# TMC2208_TEST.net
KiCad netlist of a schematic drawn in Altium Designer
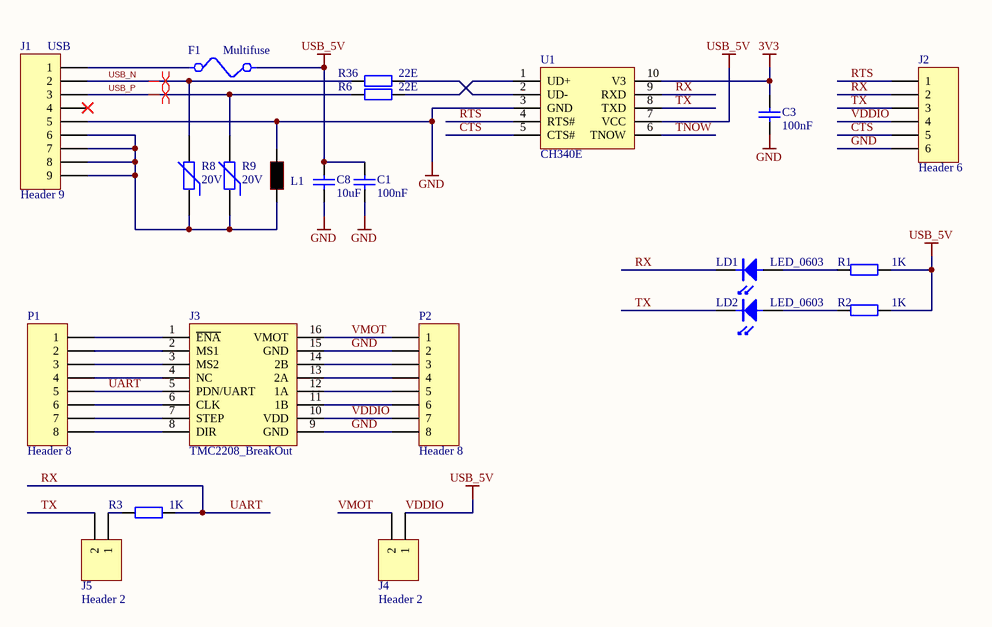
[diagram p0: TMC2208_TEST.SchDoc]

(export (version "E")
  (design (tool "Eeschema 10.0.6"))
  (components
    (comp (ref "C1")
      (value "100nF")
      (footprint "CAP0603")
      (description "RO X7R 100nF 10% 50V 0603")
      (libsource (lib "Ultimaker") (part "Capacitor"))
    )
    (comp (ref "C3")
      (value "100nF")
      (footprint "CAP0603")
      (description "RO X5R 1uF 10% 10V 0603")
      (libsource (lib "Ultimaker") (part "Capacitor"))
    )
    (comp (ref "C8")
      (value "10uF")
      (footprint "CAP0603")
      (description "RO X7R 100nF 10% 50V 0603")
      (libsource (lib "Ultimaker") (part "Capacitor"))
    )
    (comp (ref "F1")
      (value "Multifuse")
      (footprint "Multifuse1812")
      (description "RO ZEK MULTI 500MA SMD 1812 MF-MSMF050-2 BOURNS")
      (fields (field (name "MFG") "BOURNS"))
      (libsource (lib "Ultimaker") (part "Multifuse"))
    )
    (comp (ref "J1")
      (value "Header 9")
      (footprint "MicroUSB")
      (description "Header, 9-Pin")
      (fields (field (name "PUBLISHER") "Altium Limited"))
      (libsource (lib "Miscellaneous Connectors") (part "Header 9"))
    )
    (comp (ref "J2")
      (value "Header 6")
      (footprint "HDR1X6")
      (description "Header, 6-Pin")
      (fields (field (name "PUBLISHER") "Altium Limited"))
      (libsource (lib "Miscellaneous Connectors") (part "Header 6"))
    )
    (comp (ref "J3")
      (value "TMC2208_BreakOut")
      (footprint "TMC2208")
      (libsource (lib "接插件库") (part "TMC2208_BreakOut"))
    )
    (comp (ref "J4")
      (value "Header 2")
      (footprint "HDR1X2")
      (description "Header, 2-Pin")
      (fields (field (name "PUBLISHER") "Altium Limited"))
      (libsource (lib "Miscellaneous Connectors") (part "Header 2"))
    )
    (comp (ref "J5")
      (value "Header 2")
      (footprint "HDR1X2")
      (description "Header, 2-Pin")
      (fields (field (name "PUBLISHER") "Altium Limited"))
      (libsource (lib "Miscellaneous Connectors") (part "Header 2"))
    )
    (comp (ref "L1")
      (value "Bead")
      (footprint "L0805")
      (description "RO FERRIET BLM21PG221SN1D  0805")
      (libsource (lib "Ultimaker") (part "Bead"))
    )
    (comp (ref "LD1") (value "LED_0603") (footprint "LED0603") (libsource (lib "接插件库") (part "LED_0603")))
    (comp (ref "LD2") (value "LED_0603") (footprint "LED0603") (libsource (lib "接插件库") (part "LED_0603")))
    (comp (ref "P1")
      (value "Header 8")
      (footprint "Header 1X8")
      (description "Header, 8-Pin")
      (fields (field (name "PUBLISHER") "Altium Limited"))
      (libsource (lib "") (part "Header 8_1"))
    )
    (comp (ref "P2")
      (value "Header 8")
      (footprint "Header 1X8")
      (description "Header, 8-Pin")
      (fields (field (name "PUBLISHER") "Altium Limited"))
      (libsource (lib "Miscellaneous Connectors") (part "Header 8"))
    )
    (comp (ref "R1")
      (value "1K")
      (footprint "RES0603")
      (description "RO RES 22E0 1% 0,063W 0603")
      (libsource (lib "") (part "Resistor_1"))
    )
    (comp (ref "R2")
      (value "1K")
      (footprint "RES0603")
      (description "RO RES 22E0 1% 0,063W 0603")
      (libsource (lib "") (part "Resistor_1"))
    )
    (comp (ref "R3")
      (value "1K")
      (footprint "RES0603")
      (description "RO RES 22E0 1% 0,063W 0603")
      (libsource (lib "Ultimaker") (part "Resistor"))
    )
    (comp (ref "R6")
      (value "22E")
      (footprint "RES0603")
      (description "RO RES 22E0 1% 0,063W 0603")
      (libsource (lib "Ultimaker") (part "Resistor"))
    )
    (comp (ref "R8")
      (value "20V")
      (footprint "RES0603")
      (description "RO VDR 0603 CG0603MLC-05E")
      (fields (field (name "MFG") "BOURNS"))
      (libsource (lib "Ultimaker") (part "Varistor"))
    )
    (comp (ref "R9")
      (value "20V")
      (footprint "RES0603")
      (description "RO VDR 0603 CG0603MLC-05E")
      (fields (field (name "MFG") "BOURNS"))
      (libsource (lib "Ultimaker") (part "Varistor"))
    )
    (comp (ref "R36")
      (value "22E")
      (footprint "RES0603")
      (description "RO RES 22E0 1% 0,063W 0603")
      (libsource (lib "Ultimaker") (part "Resistor"))
    )
    (comp (ref "U1") (value "CH340E") (footprint "MSOP10") (libsource (lib "接插件库") (part "CH340E")))
  )
  (nets
    (net (code "1") (name "/CTS") (class "Default")
      (node (ref "J2") (pin "5") (pinfunction "5_5") (pintype "passive"))
      (node (ref "U1") (pin "5") (pinfunction "CTS#_5") (pintype "passive"))
    )
    (net (code "2") (name "/RTS") (class "Default")
      (node (ref "J2") (pin "1") (pinfunction "1_1") (pintype "passive"))
      (node (ref "U1") (pin "4") (pinfunction "RTS#_4") (pintype "passive"))
    )
    (net (code "3") (name "/RX") (class "Default")
      (node (ref "J2") (pin "2") (pinfunction "2_2") (pintype "passive"))
      (node (ref "J3") (pin "5") (pinfunction "PDN/UART_5") (pintype "passive"))
      (node (ref "LD1") (pin "1") (pinfunction "A_1") (pintype "passive"))
      (node (ref "P1") (pin "5") (pinfunction "5_5") (pintype "passive"))
      (node (ref "R3") (pin "2") (pinfunction "2_2") (pintype "passive"))
      (node (ref "U1") (pin "9") (pinfunction "RXD_9") (pintype "passive"))
    )
    (net (code "4") (name "/TNOW") (class "Default")
      (node (ref "U1") (pin "6") (pinfunction "TNOW_6") (pintype "passive"))
    )
    (net (code "5") (name "/TX") (class "Default")
      (node (ref "J2") (pin "3") (pinfunction "3_3") (pintype "passive"))
      (node (ref "J5") (pin "2") (pinfunction "2_2") (pintype "passive"))
      (node (ref "LD2") (pin "1") (pinfunction "A_1") (pintype "passive"))
      (node (ref "U1") (pin "8") (pinfunction "TXD_8") (pintype "passive"))
    )
    (net (code "6") (name "/USB_N") (class "Default")
      (node (ref "J1") (pin "2") (pinfunction "2_2") (pintype "passive"))
      (node (ref "R36") (pin "1") (pinfunction "1_1") (pintype "passive"))
      (node (ref "R8") (pin "2") (pinfunction "2_2") (pintype "passive"))
    )
    (net (code "7") (name "/USB_P") (class "Default")
      (node (ref "J1") (pin "3") (pinfunction "3_3") (pintype "passive"))
      (node (ref "R6") (pin "1") (pinfunction "1_1") (pintype "passive"))
      (node (ref "R9") (pin "2") (pinfunction "2_2") (pintype "passive"))
    )
    (net (code "8") (name "/VMOT") (class "Default")
      (node (ref "J3") (pin "16") (pinfunction "VMOT_16") (pintype "passive"))
      (node (ref "J4") (pin "2") (pinfunction "2_2") (pintype "passive"))
      (node (ref "P2") (pin "1") (pinfunction "1_1") (pintype "passive"))
    )
    (net (code "9") (name "3V3") (class "Default")
      (node (ref "C3") (pin "2") (pinfunction "2_2") (pintype "passive"))
      (node (ref "U1") (pin "10") (pinfunction "V3_10") (pintype "passive"))
    )
    (net (code "10") (name "GND") (class "Default")
      (node (ref "C1") (pin "2") (pinfunction "2_2") (pintype "passive"))
      (node (ref "C3") (pin "1") (pinfunction "1_1") (pintype "passive"))
      (node (ref "C8") (pin "1") (pinfunction "1_1") (pintype "passive"))
      (node (ref "J1") (pin "5") (pinfunction "5_5") (pintype "passive"))
      (node (ref "J2") (pin "6") (pinfunction "6_6") (pintype "passive"))
      (node (ref "J3") (pin "15") (pinfunction "GND_15") (pintype "passive"))
      (node (ref "J3") (pin "9") (pinfunction "GND_9") (pintype "passive"))
      (node (ref "L1") (pin "1") (pinfunction "1_1") (pintype "passive"))
      (node (ref "P2") (pin "2") (pinfunction "2_2") (pintype "passive"))
      (node (ref "P2") (pin "8") (pinfunction "8_8") (pintype "passive"))
      (node (ref "U1") (pin "3") (pinfunction "GND_3") (pintype "passive"))
    )
    (net (code "11") (name "Net-(F1-Pad1)") (class "Default")
      (node (ref "F1") (pin "1") (pinfunction "1_1") (pintype "passive"))
      (node (ref "J1") (pin "1") (pinfunction "1_1") (pintype "passive"))
    )
    (net (code "12") (name "Net-(J1-Pad6)") (class "Default")
      (node (ref "J1") (pin "6") (pinfunction "6_6") (pintype "passive"))
      (node (ref "J1") (pin "7") (pinfunction "7_7") (pintype "passive"))
      (node (ref "J1") (pin "8") (pinfunction "8_8") (pintype "passive"))
      (node (ref "J1") (pin "9") (pinfunction "9_9") (pintype "passive"))
      (node (ref "L1") (pin "2") (pinfunction "2_2") (pintype "passive"))
      (node (ref "R8") (pin "1") (pinfunction "1_1") (pintype "passive"))
      (node (ref "R9") (pin "1") (pinfunction "1_1") (pintype "passive"))
    )
    (net (code "13") (name "Net-(J3-1A)") (class "Default")
      (node (ref "J3") (pin "12") (pinfunction "1A_12") (pintype "passive"))
      (node (ref "P2") (pin "5") (pinfunction "5_5") (pintype "passive"))
    )
    (net (code "14") (name "Net-(J3-1B)") (class "Default")
      (node (ref "J3") (pin "11") (pinfunction "1B_11") (pintype "passive"))
      (node (ref "P2") (pin "6") (pinfunction "6_6") (pintype "passive"))
    )
    (net (code "15") (name "Net-(J3-2A)") (class "Default")
      (node (ref "J3") (pin "13") (pinfunction "2A_13") (pintype "passive"))
      (node (ref "P2") (pin "4") (pinfunction "4_4") (pintype "passive"))
    )
    (net (code "16") (name "Net-(J3-2B)") (class "Default")
      (node (ref "J3") (pin "14") (pinfunction "2B_14") (pintype "passive"))
      (node (ref "P2") (pin "3") (pinfunction "3_3") (pintype "passive"))
    )
    (net (code "17") (name "Net-(J3-CLK)") (class "Default")
      (node (ref "J3") (pin "6") (pinfunction "CLK_6") (pintype "passive"))
      (node (ref "P1") (pin "6") (pinfunction "6_6") (pintype "passive"))
    )
    (net (code "18") (name "Net-(J3-DIR)") (class "Default")
      (node (ref "J3") (pin "8") (pinfunction "DIR_8") (pintype "passive"))
      (node (ref "P1") (pin "8") (pinfunction "8_8") (pintype "passive"))
    )
    (net (code "19") (name "Net-(J3-MS1)") (class "Default")
      (node (ref "J3") (pin "2") (pinfunction "MS1_2") (pintype "passive"))
      (node (ref "P1") (pin "2") (pinfunction "2_2") (pintype "passive"))
    )
    (net (code "20") (name "Net-(J3-MS2)") (class "Default")
      (node (ref "J3") (pin "3") (pinfunction "MS2_3") (pintype "passive"))
      (node (ref "P1") (pin "3") (pinfunction "3_3") (pintype "passive"))
    )
    (net (code "21") (name "Net-(J3-NC)") (class "Default")
      (node (ref "J3") (pin "4") (pinfunction "NC_4") (pintype "passive"))
      (node (ref "P1") (pin "4") (pinfunction "4_4") (pintype "passive"))
    )
    (net (code "22") (name "Net-(J3-STEP)") (class "Default")
      (node (ref "J3") (pin "7") (pinfunction "STEP_7") (pintype "passive"))
      (node (ref "P1") (pin "7") (pinfunction "7_7") (pintype "passive"))
    )
    (net (code "23") (name "Net-(J3-~{ENA})") (class "Default")
      (node (ref "J3") (pin "1") (pinfunction "~{ENA}_1") (pintype "passive"))
      (node (ref "P1") (pin "1") (pinfunction "1_1") (pintype "passive"))
    )
    (net (code "24") (name "Net-(J5-Pad1)") (class "Default")
      (node (ref "J5") (pin "1") (pinfunction "1_1") (pintype "passive"))
      (node (ref "R3") (pin "1") (pinfunction "1_1") (pintype "passive"))
    )
    (net (code "25") (name "Net-(LD1-K)") (class "Default")
      (node (ref "LD1") (pin "2") (pinfunction "K_2") (pintype "passive"))
      (node (ref "R1") (pin "2") (pinfunction "2_2") (pintype "passive"))
    )
    (net (code "26") (name "Net-(LD2-K)") (class "Default")
      (node (ref "LD2") (pin "2") (pinfunction "K_2") (pintype "passive"))
      (node (ref "R2") (pin "2") (pinfunction "2_2") (pintype "passive"))
    )
    (net (code "27") (name "Net-(U1-UD+)") (class "Default")
      (node (ref "R6") (pin "2") (pinfunction "2_2") (pintype "passive"))
      (node (ref "U1") (pin "1") (pinfunction "UD+_1") (pintype "passive"))
    )
    (net (code "28") (name "Net-(U1-UD-)") (class "Default")
      (node (ref "R36") (pin "2") (pinfunction "2_2") (pintype "passive"))
      (node (ref "U1") (pin "2") (pinfunction "UD-_2") (pintype "passive"))
    )
    (net (code "29") (name "USB_5V") (class "Default")
      (node (ref "C1") (pin "1") (pinfunction "1_1") (pintype "passive"))
      (node (ref "C8") (pin "2") (pinfunction "2_2") (pintype "passive"))
      (node (ref "F1") (pin "2") (pinfunction "2_2") (pintype "passive"))
      (node (ref "J2") (pin "4") (pinfunction "4_4") (pintype "passive"))
      (node (ref "J3") (pin "10") (pinfunction "VDD_10") (pintype "passive"))
      (node (ref "J4") (pin "1") (pinfunction "1_1") (pintype "passive"))
      (node (ref "P2") (pin "7") (pinfunction "7_7") (pintype "passive"))
      (node (ref "R1") (pin "1") (pinfunction "1_1") (pintype "passive"))
      (node (ref "R2") (pin "1") (pinfunction "1_1") (pintype "passive"))
      (node (ref "U1") (pin "7") (pinfunction "VCC_7") (pintype "passive"))
    )
    (net (code "30") (name "unconnected-(J1-Pad4)") (class "Default")
      (node (ref "J1") (pin "4") (pinfunction "4_4") (pintype "passive+no_connect"))
    )
  )
)
